# RS485_CV_FT4232H.net
KiCad netlist of a schematic drawn in EAGLE
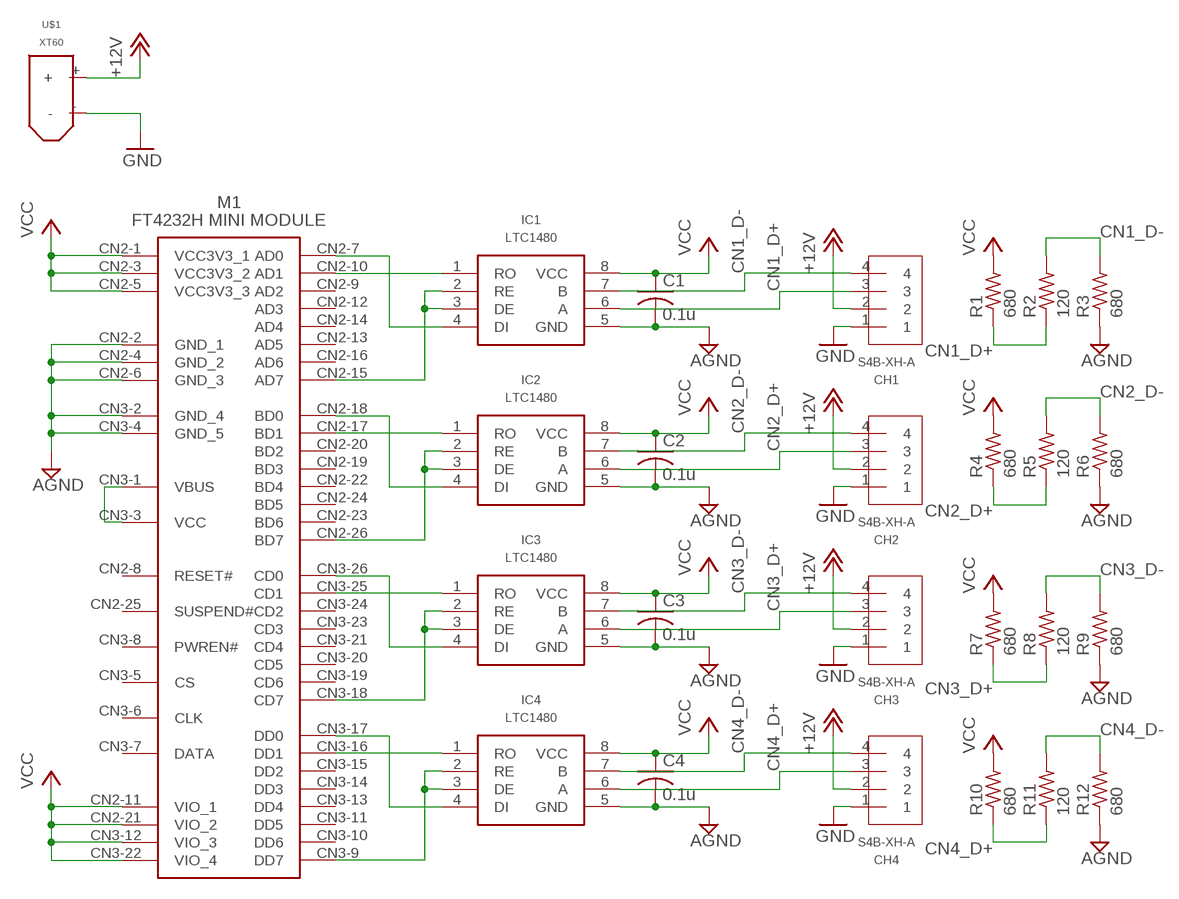
[diagram p0: schematic, sheet 1]

(export (version "E")
  (design (tool "Eeschema 10.0.6"))
  (components
    (comp (ref "C1")
      (value "0.1u")
      (footprint "eagle-import:C0603")
      (libsource (lib "eagle-import") (part "C-USC0603"))
    )
    (comp (ref "C2")
      (value "0.1u")
      (footprint "eagle-import:C0603")
      (libsource (lib "eagle-import") (part "C-USC0603"))
    )
    (comp (ref "C3")
      (value "0.1u")
      (footprint "eagle-import:C0603")
      (libsource (lib "eagle-import") (part "C-USC0603"))
    )
    (comp (ref "C4")
      (value "0.1u")
      (footprint "eagle-import:C0603")
      (libsource (lib "eagle-import") (part "C-USC0603"))
    )
    (comp (ref "CH1")
      (value "S4B-XH-A")
      (footprint "eagle-import:S4B-XH-A")
      (libsource (lib "eagle-import") (part "S4B-XH-A"))
    )
    (comp (ref "CH2")
      (value "S4B-XH-A")
      (footprint "eagle-import:S4B-XH-A")
      (libsource (lib "eagle-import") (part "S4B-XH-A"))
    )
    (comp (ref "CH3")
      (value "S4B-XH-A")
      (footprint "eagle-import:S4B-XH-A")
      (libsource (lib "eagle-import") (part "S4B-XH-A"))
    )
    (comp (ref "CH4")
      (value "S4B-XH-A")
      (footprint "eagle-import:S4B-XH-A")
      (libsource (lib "eagle-import") (part "S4B-XH-A"))
    )
    (comp (ref "IC1")
      (value "LTC1480")
      (footprint "eagle-import:LTC1480")
      (libsource (lib "eagle-import") (part "LTC1480"))
    )
    (comp (ref "IC2")
      (value "LTC1480")
      (footprint "eagle-import:LTC1480")
      (libsource (lib "eagle-import") (part "LTC1480"))
    )
    (comp (ref "IC3")
      (value "LTC1480")
      (footprint "eagle-import:LTC1480")
      (libsource (lib "eagle-import") (part "LTC1480"))
    )
    (comp (ref "IC4")
      (value "LTC1480")
      (footprint "eagle-import:LTC1480")
      (libsource (lib "eagle-import") (part "LTC1480"))
    )
    (comp (ref "M1")
      (value "FT4232H_MINI_MODULE")
      (footprint "eagle-import:FT4232H_MINI_MODULE")
      (libsource (lib "eagle-import") (part "FT4232H_MINI_MODULE"))
    )
    (comp (ref "R1")
      (value "680")
      (footprint "eagle-import:R0603")
      (libsource (lib "eagle-import") (part "R-US_R0603"))
    )
    (comp (ref "R2")
      (value "120")
      (footprint "eagle-import:R0603")
      (libsource (lib "eagle-import") (part "R-US_R0603"))
    )
    (comp (ref "R3")
      (value "680")
      (footprint "eagle-import:R0603")
      (libsource (lib "eagle-import") (part "R-US_R0603"))
    )
    (comp (ref "R4")
      (value "680")
      (footprint "eagle-import:R0603")
      (libsource (lib "eagle-import") (part "R-US_R0603"))
    )
    (comp (ref "R5")
      (value "120")
      (footprint "eagle-import:R0603")
      (libsource (lib "eagle-import") (part "R-US_R0603"))
    )
    (comp (ref "R6")
      (value "680")
      (footprint "eagle-import:R0603")
      (libsource (lib "eagle-import") (part "R-US_R0603"))
    )
    (comp (ref "R7")
      (value "680")
      (footprint "eagle-import:R0603")
      (libsource (lib "eagle-import") (part "R-US_R0603"))
    )
    (comp (ref "R8")
      (value "120")
      (footprint "eagle-import:R0603")
      (libsource (lib "eagle-import") (part "R-US_R0603"))
    )
    (comp (ref "R9")
      (value "680")
      (footprint "eagle-import:R0603")
      (libsource (lib "eagle-import") (part "R-US_R0603"))
    )
    (comp (ref "R10")
      (value "680")
      (footprint "eagle-import:R0603")
      (libsource (lib "eagle-import") (part "R-US_R0603"))
    )
    (comp (ref "R11")
      (value "120")
      (footprint "eagle-import:R0603")
      (libsource (lib "eagle-import") (part "R-US_R0603"))
    )
    (comp (ref "R12")
      (value "680")
      (footprint "eagle-import:R0603")
      (libsource (lib "eagle-import") (part "R-US_R0603"))
    )
    (comp (ref "U$1")
      (value "XT60PT-M")
      (footprint "eagle-import:XT60PT-M")
      (libsource (lib "eagle-import") (part "XT60PT-M"))
    )
  )
  (nets
    (net (code "1") (name "+12V") (class "Default")
      (node (ref "CH1") (pin "2") (pinfunction "2_2") (pintype "bidirectional"))
      (node (ref "CH2") (pin "2") (pinfunction "2_2") (pintype "bidirectional"))
      (node (ref "CH3") (pin "2") (pinfunction "2_2") (pintype "bidirectional"))
      (node (ref "CH4") (pin "2") (pinfunction "2_2") (pintype "bidirectional"))
      (node (ref "U$1") (pin "+") (pinfunction "+_+") (pintype "power_in"))
    )
    (net (code "2") (name "/CN1_D+") (class "Default")
      (node (ref "CH1") (pin "3") (pinfunction "3_3") (pintype "bidirectional"))
      (node (ref "IC1") (pin "6") (pinfunction "A_6") (pintype "bidirectional"))
      (node (ref "R1") (pin "1") (pinfunction "1_1") (pintype "passive"))
      (node (ref "R2") (pin "1") (pinfunction "1_1") (pintype "passive"))
    )
    (net (code "3") (name "/CN1_D-") (class "Default")
      (node (ref "CH1") (pin "4") (pinfunction "4_4") (pintype "bidirectional"))
      (node (ref "IC1") (pin "7") (pinfunction "B_7") (pintype "bidirectional"))
      (node (ref "R2") (pin "2") (pinfunction "2_2") (pintype "passive"))
      (node (ref "R3") (pin "2") (pinfunction "2_2") (pintype "passive"))
    )
    (net (code "4") (name "/CN2_D+") (class "Default")
      (node (ref "CH2") (pin "3") (pinfunction "3_3") (pintype "bidirectional"))
      (node (ref "IC2") (pin "6") (pinfunction "A_6") (pintype "bidirectional"))
      (node (ref "R4") (pin "1") (pinfunction "1_1") (pintype "passive"))
      (node (ref "R5") (pin "1") (pinfunction "1_1") (pintype "passive"))
    )
    (net (code "5") (name "/CN2_D-") (class "Default")
      (node (ref "CH2") (pin "4") (pinfunction "4_4") (pintype "bidirectional"))
      (node (ref "IC2") (pin "7") (pinfunction "B_7") (pintype "bidirectional"))
      (node (ref "R5") (pin "2") (pinfunction "2_2") (pintype "passive"))
      (node (ref "R6") (pin "2") (pinfunction "2_2") (pintype "passive"))
    )
    (net (code "6") (name "/CN3_D+") (class "Default")
      (node (ref "CH3") (pin "3") (pinfunction "3_3") (pintype "bidirectional"))
      (node (ref "IC3") (pin "6") (pinfunction "A_6") (pintype "bidirectional"))
      (node (ref "R7") (pin "1") (pinfunction "1_1") (pintype "passive"))
      (node (ref "R8") (pin "1") (pinfunction "1_1") (pintype "passive"))
    )
    (net (code "7") (name "/CN3_D-") (class "Default")
      (node (ref "CH3") (pin "4") (pinfunction "4_4") (pintype "bidirectional"))
      (node (ref "IC3") (pin "7") (pinfunction "B_7") (pintype "bidirectional"))
      (node (ref "R8") (pin "2") (pinfunction "2_2") (pintype "passive"))
      (node (ref "R9") (pin "2") (pinfunction "2_2") (pintype "passive"))
    )
    (net (code "8") (name "/CN4_D+") (class "Default")
      (node (ref "CH4") (pin "3") (pinfunction "3_3") (pintype "bidirectional"))
      (node (ref "IC4") (pin "6") (pinfunction "A_6") (pintype "bidirectional"))
      (node (ref "R10") (pin "1") (pinfunction "1_1") (pintype "passive"))
      (node (ref "R11") (pin "1") (pinfunction "1_1") (pintype "passive"))
    )
    (net (code "9") (name "/CN4_D-") (class "Default")
      (node (ref "CH4") (pin "4") (pinfunction "4_4") (pintype "bidirectional"))
      (node (ref "IC4") (pin "7") (pinfunction "B_7") (pintype "bidirectional"))
      (node (ref "R11") (pin "2") (pinfunction "2_2") (pintype "passive"))
      (node (ref "R12") (pin "2") (pinfunction "2_2") (pintype "passive"))
    )
    (net (code "10") (name "AGND") (class "Default")
      (node (ref "C1") (pin "2") (pinfunction "2_2") (pintype "passive"))
      (node (ref "C2") (pin "2") (pinfunction "2_2") (pintype "passive"))
      (node (ref "C3") (pin "2") (pinfunction "2_2") (pintype "passive"))
      (node (ref "C4") (pin "2") (pinfunction "2_2") (pintype "passive"))
      (node (ref "IC1") (pin "5") (pinfunction "GND_5") (pintype "bidirectional"))
      (node (ref "IC2") (pin "5") (pinfunction "GND_5") (pintype "bidirectional"))
      (node (ref "IC3") (pin "5") (pinfunction "GND_5") (pintype "bidirectional"))
      (node (ref "IC4") (pin "5") (pinfunction "GND_5") (pintype "bidirectional"))
      (node (ref "M1") (pin "CN2-2") (pinfunction "GND_1_CN2-2") (pintype "bidirectional"))
      (node (ref "M1") (pin "CN2-4") (pinfunction "GND_2_CN2-4") (pintype "bidirectional"))
      (node (ref "M1") (pin "CN2-6") (pinfunction "GND_3_CN2-6") (pintype "bidirectional"))
      (node (ref "M1") (pin "CN3-2") (pinfunction "GND_4_CN3-2") (pintype "bidirectional"))
      (node (ref "M1") (pin "CN3-4") (pinfunction "GND_5_CN3-4") (pintype "bidirectional"))
      (node (ref "R12") (pin "1") (pinfunction "1_1") (pintype "passive"))
      (node (ref "R3") (pin "1") (pinfunction "1_1") (pintype "passive"))
      (node (ref "R6") (pin "1") (pinfunction "1_1") (pintype "passive"))
      (node (ref "R9") (pin "1") (pinfunction "1_1") (pintype "passive"))
    )
    (net (code "11") (name "GND") (class "Default")
      (node (ref "CH1") (pin "1") (pinfunction "1_1") (pintype "bidirectional"))
      (node (ref "CH2") (pin "1") (pinfunction "1_1") (pintype "bidirectional"))
      (node (ref "CH3") (pin "1") (pinfunction "1_1") (pintype "bidirectional"))
      (node (ref "CH4") (pin "1") (pinfunction "1_1") (pintype "bidirectional"))
      (node (ref "U$1") (pin "-") (pinfunction "-_-") (pintype "power_in"))
    )
    (net (code "12") (name "Net-(IC1-DE)") (class "Default")
      (node (ref "IC1") (pin "2") (pinfunction "RE_2") (pintype "bidirectional"))
      (node (ref "IC1") (pin "3") (pinfunction "DE_3") (pintype "bidirectional"))
      (node (ref "M1") (pin "CN2-15") (pinfunction "AD7_CN2-15") (pintype "bidirectional"))
    )
    (net (code "13") (name "Net-(IC1-DI)") (class "Default")
      (node (ref "IC1") (pin "4") (pinfunction "DI_4") (pintype "bidirectional"))
      (node (ref "M1") (pin "CN2-7") (pinfunction "AD0_CN2-7") (pintype "bidirectional"))
    )
    (net (code "14") (name "Net-(IC1-RO)") (class "Default")
      (node (ref "IC1") (pin "1") (pinfunction "RO_1") (pintype "bidirectional"))
      (node (ref "M1") (pin "CN2-10") (pinfunction "AD1_CN2-10") (pintype "bidirectional"))
    )
    (net (code "15") (name "Net-(IC2-DE)") (class "Default")
      (node (ref "IC2") (pin "2") (pinfunction "RE_2") (pintype "bidirectional"))
      (node (ref "IC2") (pin "3") (pinfunction "DE_3") (pintype "bidirectional"))
      (node (ref "M1") (pin "CN2-26") (pinfunction "BD7_CN2-26") (pintype "bidirectional"))
    )
    (net (code "16") (name "Net-(IC2-DI)") (class "Default")
      (node (ref "IC2") (pin "4") (pinfunction "DI_4") (pintype "bidirectional"))
      (node (ref "M1") (pin "CN2-18") (pinfunction "BD0_CN2-18") (pintype "bidirectional"))
    )
    (net (code "17") (name "Net-(IC2-RO)") (class "Default")
      (node (ref "IC2") (pin "1") (pinfunction "RO_1") (pintype "bidirectional"))
      (node (ref "M1") (pin "CN2-17") (pinfunction "BD1_CN2-17") (pintype "bidirectional"))
    )
    (net (code "18") (name "Net-(IC3-DE)") (class "Default")
      (node (ref "IC3") (pin "2") (pinfunction "RE_2") (pintype "bidirectional"))
      (node (ref "IC3") (pin "3") (pinfunction "DE_3") (pintype "bidirectional"))
      (node (ref "M1") (pin "CN3-18") (pinfunction "CD7_CN3-18") (pintype "bidirectional"))
    )
    (net (code "19") (name "Net-(IC3-DI)") (class "Default")
      (node (ref "IC3") (pin "4") (pinfunction "DI_4") (pintype "bidirectional"))
      (node (ref "M1") (pin "CN3-26") (pinfunction "CD0_CN3-26") (pintype "bidirectional"))
    )
    (net (code "20") (name "Net-(IC3-RO)") (class "Default")
      (node (ref "IC3") (pin "1") (pinfunction "RO_1") (pintype "bidirectional"))
      (node (ref "M1") (pin "CN3-25") (pinfunction "CD1_CN3-25") (pintype "bidirectional"))
    )
    (net (code "21") (name "Net-(IC4-DE)") (class "Default")
      (node (ref "IC4") (pin "2") (pinfunction "RE_2") (pintype "bidirectional"))
      (node (ref "IC4") (pin "3") (pinfunction "DE_3") (pintype "bidirectional"))
      (node (ref "M1") (pin "CN3-9") (pinfunction "DD7_CN3-9") (pintype "bidirectional"))
    )
    (net (code "22") (name "Net-(IC4-DI)") (class "Default")
      (node (ref "IC4") (pin "4") (pinfunction "DI_4") (pintype "bidirectional"))
      (node (ref "M1") (pin "CN3-17") (pinfunction "DD0_CN3-17") (pintype "bidirectional"))
    )
    (net (code "23") (name "Net-(IC4-RO)") (class "Default")
      (node (ref "IC4") (pin "1") (pinfunction "RO_1") (pintype "bidirectional"))
      (node (ref "M1") (pin "CN3-16") (pinfunction "DD1_CN3-16") (pintype "bidirectional"))
    )
    (net (code "24") (name "Net-(M1-VBUS)") (class "Default")
      (node (ref "M1") (pin "CN3-1") (pinfunction "VBUS_CN3-1") (pintype "bidirectional"))
      (node (ref "M1") (pin "CN3-3") (pinfunction "VCC_CN3-3") (pintype "bidirectional"))
    )
    (net (code "25") (name "VCC") (class "Default")
      (node (ref "C1") (pin "1") (pinfunction "1_1") (pintype "passive"))
      (node (ref "C2") (pin "1") (pinfunction "1_1") (pintype "passive"))
      (node (ref "C3") (pin "1") (pinfunction "1_1") (pintype "passive"))
      (node (ref "C4") (pin "1") (pinfunction "1_1") (pintype "passive"))
      (node (ref "IC1") (pin "8") (pinfunction "VCC_8") (pintype "bidirectional"))
      (node (ref "IC2") (pin "8") (pinfunction "VCC_8") (pintype "bidirectional"))
      (node (ref "IC3") (pin "8") (pinfunction "VCC_8") (pintype "bidirectional"))
      (node (ref "IC4") (pin "8") (pinfunction "VCC_8") (pintype "bidirectional"))
      (node (ref "M1") (pin "CN2-1") (pinfunction "VCC3V3_1_CN2-1") (pintype "bidirectional"))
      (node (ref "M1") (pin "CN2-11") (pinfunction "VIO_1_CN2-11") (pintype "bidirectional"))
      (node (ref "M1") (pin "CN2-21") (pinfunction "VIO_2_CN2-21") (pintype "bidirectional"))
      (node (ref "M1") (pin "CN2-3") (pinfunction "VCC3V3_2_CN2-3") (pintype "bidirectional"))
      (node (ref "M1") (pin "CN2-5") (pinfunction "VCC3V3_3_CN2-5") (pintype "bidirectional"))
      (node (ref "M1") (pin "CN3-12") (pinfunction "VIO_3_CN3-12") (pintype "bidirectional"))
      (node (ref "M1") (pin "CN3-22") (pinfunction "VIO_4_CN3-22") (pintype "bidirectional"))
      (node (ref "R1") (pin "2") (pinfunction "2_2") (pintype "passive"))
      (node (ref "R10") (pin "2") (pinfunction "2_2") (pintype "passive"))
      (node (ref "R4") (pin "2") (pinfunction "2_2") (pintype "passive"))
      (node (ref "R7") (pin "2") (pinfunction "2_2") (pintype "passive"))
    )
    (net (code "26") (name "unconnected-(M1-AD2-PadCN2-9)") (class "Default")
      (node (ref "M1") (pin "CN2-9") (pinfunction "AD2_CN2-9") (pintype "bidirectional"))
    )
    (net (code "27") (name "unconnected-(M1-AD3-PadCN2-12)") (class "Default")
      (node (ref "M1") (pin "CN2-12") (pinfunction "AD3_CN2-12") (pintype "bidirectional"))
    )
    (net (code "28") (name "unconnected-(M1-AD4-PadCN2-14)") (class "Default")
      (node (ref "M1") (pin "CN2-14") (pinfunction "AD4_CN2-14") (pintype "bidirectional"))
    )
    (net (code "29") (name "unconnected-(M1-AD5-PadCN2-13)") (class "Default")
      (node (ref "M1") (pin "CN2-13") (pinfunction "AD5_CN2-13") (pintype "bidirectional"))
    )
    (net (code "30") (name "unconnected-(M1-AD6-PadCN2-16)") (class "Default")
      (node (ref "M1") (pin "CN2-16") (pinfunction "AD6_CN2-16") (pintype "bidirectional"))
    )
    (net (code "31") (name "unconnected-(M1-BD2-PadCN2-20)") (class "Default")
      (node (ref "M1") (pin "CN2-20") (pinfunction "BD2_CN2-20") (pintype "bidirectional"))
    )
    (net (code "32") (name "unconnected-(M1-BD3-PadCN2-19)") (class "Default")
      (node (ref "M1") (pin "CN2-19") (pinfunction "BD3_CN2-19") (pintype "bidirectional"))
    )
    (net (code "33") (name "unconnected-(M1-BD4-PadCN2-22)") (class "Default")
      (node (ref "M1") (pin "CN2-22") (pinfunction "BD4_CN2-22") (pintype "bidirectional"))
    )
    (net (code "34") (name "unconnected-(M1-BD5-PadCN2-24)") (class "Default")
      (node (ref "M1") (pin "CN2-24") (pinfunction "BD5_CN2-24") (pintype "bidirectional"))
    )
    (net (code "35") (name "unconnected-(M1-BD6-PadCN2-23)") (class "Default")
      (node (ref "M1") (pin "CN2-23") (pinfunction "BD6_CN2-23") (pintype "bidirectional"))
    )
    (net (code "36") (name "unconnected-(M1-CD2-PadCN3-24)") (class "Default")
      (node (ref "M1") (pin "CN3-24") (pinfunction "CD2_CN3-24") (pintype "bidirectional"))
    )
    (net (code "37") (name "unconnected-(M1-CD3-PadCN3-23)") (class "Default")
      (node (ref "M1") (pin "CN3-23") (pinfunction "CD3_CN3-23") (pintype "bidirectional"))
    )
    (net (code "38") (name "unconnected-(M1-CD4-PadCN3-21)") (class "Default")
      (node (ref "M1") (pin "CN3-21") (pinfunction "CD4_CN3-21") (pintype "bidirectional"))
    )
    (net (code "39") (name "unconnected-(M1-CD5-PadCN3-20)") (class "Default")
      (node (ref "M1") (pin "CN3-20") (pinfunction "CD5_CN3-20") (pintype "bidirectional"))
    )
    (net (code "40") (name "unconnected-(M1-CD6-PadCN3-19)") (class "Default")
      (node (ref "M1") (pin "CN3-19") (pinfunction "CD6_CN3-19") (pintype "bidirectional"))
    )
    (net (code "41") (name "unconnected-(M1-CLK-PadCN3-6)") (class "Default")
      (node (ref "M1") (pin "CN3-6") (pinfunction "CLK_CN3-6") (pintype "bidirectional"))
    )
    (net (code "42") (name "unconnected-(M1-CS-PadCN3-5)") (class "Default")
      (node (ref "M1") (pin "CN3-5") (pinfunction "CS_CN3-5") (pintype "bidirectional"))
    )
    (net (code "43") (name "unconnected-(M1-DATA-PadCN3-7)") (class "Default")
      (node (ref "M1") (pin "CN3-7") (pinfunction "DATA_CN3-7") (pintype "bidirectional"))
    )
    (net (code "44") (name "unconnected-(M1-DD2-PadCN3-15)") (class "Default")
      (node (ref "M1") (pin "CN3-15") (pinfunction "DD2_CN3-15") (pintype "bidirectional"))
    )
    (net (code "45") (name "unconnected-(M1-DD3-PadCN3-14)") (class "Default")
      (node (ref "M1") (pin "CN3-14") (pinfunction "DD3_CN3-14") (pintype "bidirectional"))
    )
    (net (code "46") (name "unconnected-(M1-DD4-PadCN3-13)") (class "Default")
      (node (ref "M1") (pin "CN3-13") (pinfunction "DD4_CN3-13") (pintype "bidirectional"))
    )
    (net (code "47") (name "unconnected-(M1-DD5-PadCN3-11)") (class "Default")
      (node (ref "M1") (pin "CN3-11") (pinfunction "DD5_CN3-11") (pintype "bidirectional"))
    )
    (net (code "48") (name "unconnected-(M1-DD6-PadCN3-10)") (class "Default")
      (node (ref "M1") (pin "CN3-10") (pinfunction "DD6_CN3-10") (pintype "bidirectional"))
    )
    (net (code "49") (name "unconnected-(M1-PWREN#-PadCN3-8)") (class "Default")
      (node (ref "M1") (pin "CN3-8") (pinfunction "PWREN#_CN3-8") (pintype "bidirectional"))
    )
    (net (code "50") (name "unconnected-(M1-RESET#-PadCN2-8)") (class "Default")
      (node (ref "M1") (pin "CN2-8") (pinfunction "RESET#_CN2-8") (pintype "bidirectional"))
    )
    (net (code "51") (name "unconnected-(M1-SUSPEND#-PadCN2-25)") (class "Default")
      (node (ref "M1") (pin "CN2-25") (pinfunction "SUSPEND#_CN2-25") (pintype "bidirectional"))
    )
  )
)
